# Micromouse_controller_v008.net
KiCad netlist of a schematic drawn in EAGLE
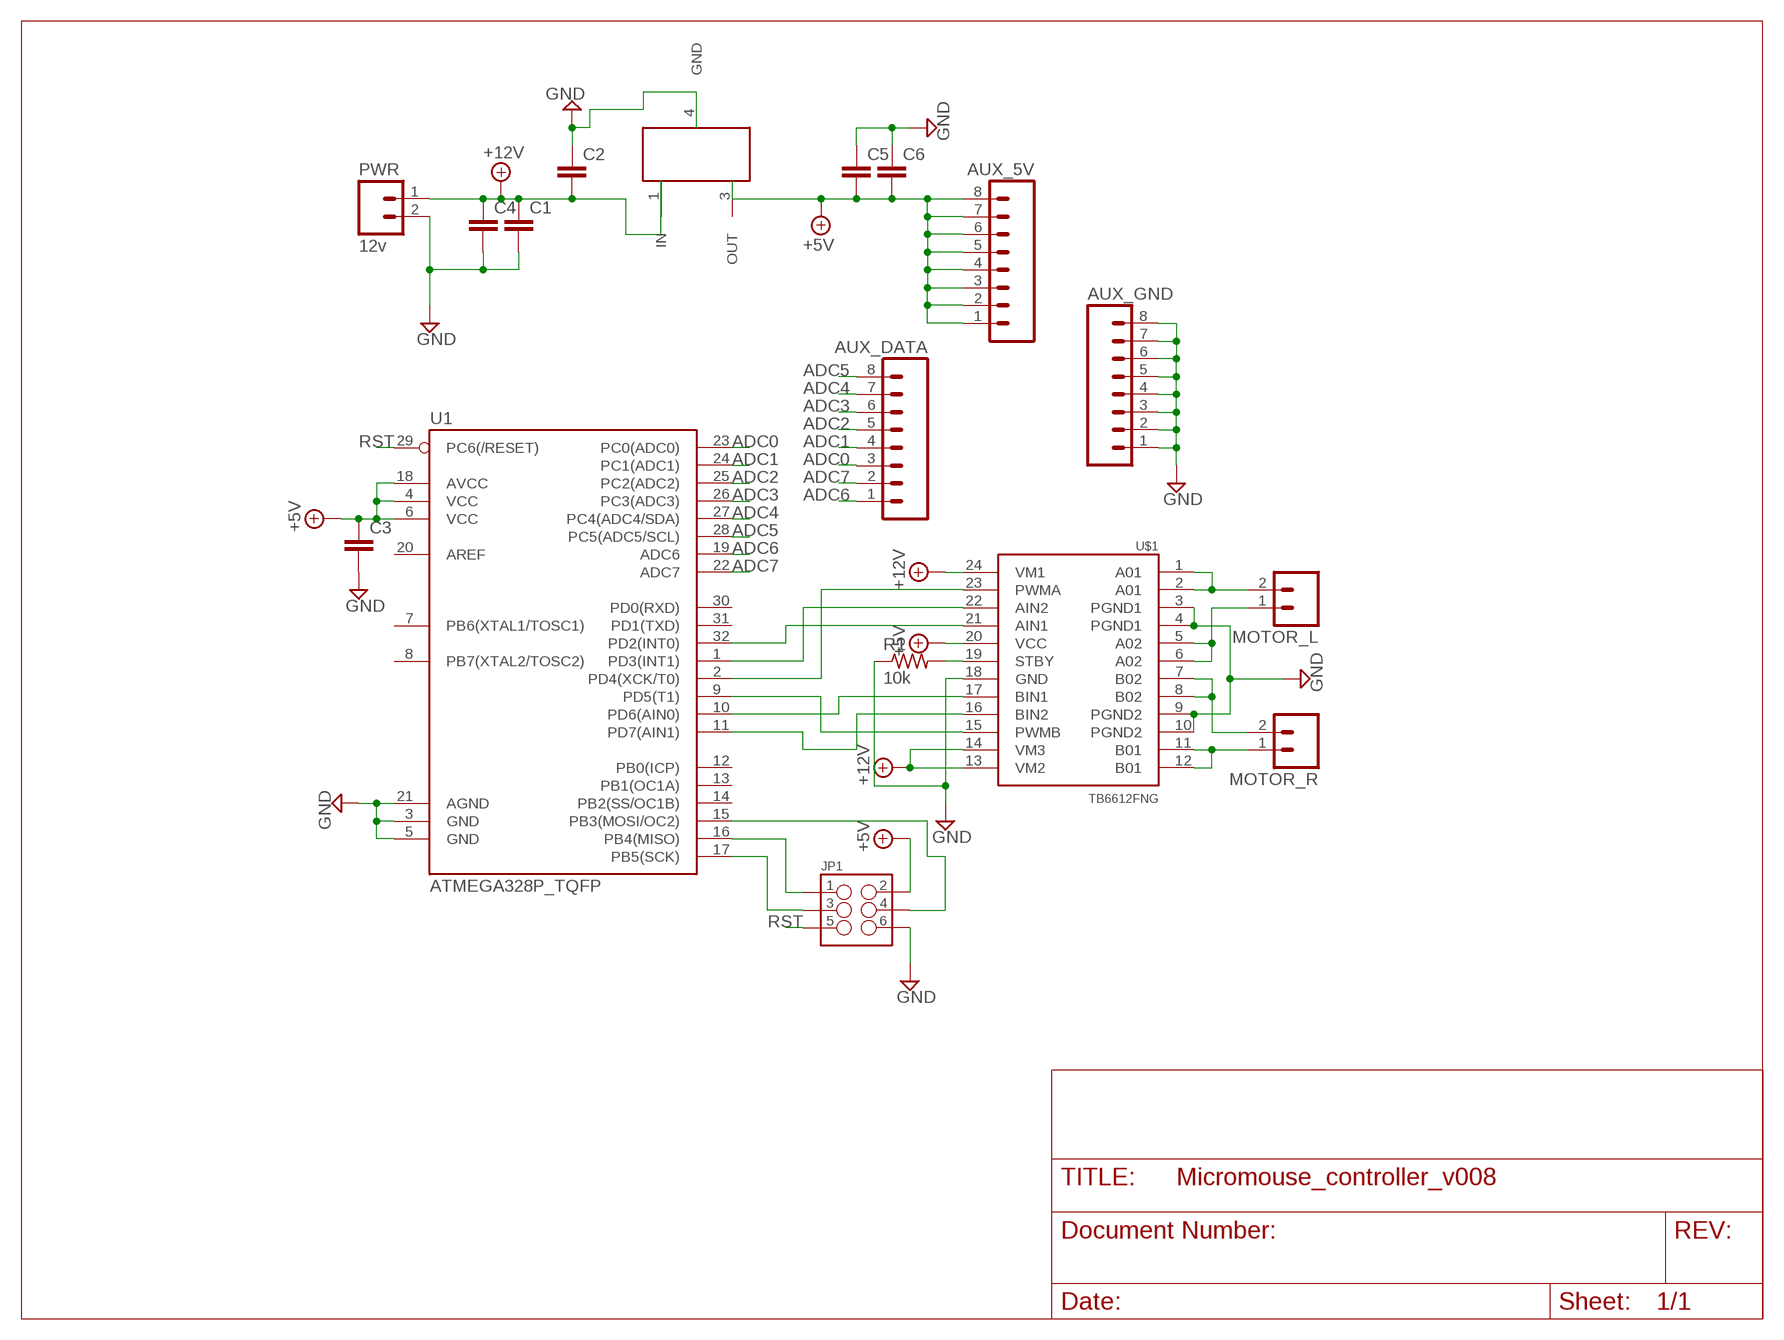
[diagram p0: schematic, sheet 1]

(export (version "E")
  (design (tool "Eeschema 10.0.6"))
  (components
    (comp (ref "AUX_5V")
      (value "M08SMD-STRAIGHT-ALT-FEMALE")
      (footprint "eagle-import:1X08_SMD_ALT")
      (libsource (lib "eagle-import") (part "M08SMD-STRAIGHT-ALT-FEMALE"))
    )
    (comp (ref "AUX_DATA")
      (value "M08SMD-STRAIGHT-ALT-FEMALE")
      (footprint "eagle-import:1X08_SMD_ALT")
      (libsource (lib "eagle-import") (part "M08SMD-STRAIGHT-ALT-FEMALE"))
    )
    (comp (ref "AUX_GND")
      (value "M08SMD-STRAIGHT-ALT-FEMALE")
      (footprint "eagle-import:1X08_SMD_ALT")
      (libsource (lib "eagle-import") (part "M08SMD-STRAIGHT-ALT-FEMALE"))
    )
    (comp (ref "C1")
      (value "CAPSMD")
      (footprint "eagle-import:GRM43D")
      (libsource (lib "eagle-import") (part "CAPSMD"))
    )
    (comp (ref "C2")
      (value "CAPSMD")
      (footprint "eagle-import:GRM43D")
      (libsource (lib "eagle-import") (part "CAPSMD"))
    )
    (comp (ref "C3")
      (value "CAPSMD")
      (footprint "eagle-import:GRM43D")
      (libsource (lib "eagle-import") (part "CAPSMD"))
    )
    (comp (ref "C4")
      (value "CAPSMD")
      (footprint "eagle-import:GRM43D")
      (libsource (lib "eagle-import") (part "CAPSMD"))
    )
    (comp (ref "C5")
      (value "CAPSMD")
      (footprint "eagle-import:GRM43D")
      (libsource (lib "eagle-import") (part "CAPSMD"))
    )
    (comp (ref "C6")
      (value "CAPSMD")
      (footprint "eagle-import:GRM43D")
      (libsource (lib "eagle-import") (part "CAPSMD"))
    )
    (comp (ref "IC2")
      (value "TA4805BF")
      (footprint "eagle-import:DPAK")
      (libsource (lib "eagle-import") (part "TA4805BF"))
    )
    (comp (ref "JP1")
      (value "M03X2FEMALE_SMD")
      (footprint "eagle-import:2X3_SMD")
      (libsource (lib "eagle-import") (part "M03X2FEMALE_SMD"))
    )
    (comp (ref "MOTOR_L")
      (value "M02-JST-2MM-SMT")
      (footprint "eagle-import:JST-2-SMD")
      (libsource (lib "eagle-import") (part "M02-JST-2MM-SMT"))
    )
    (comp (ref "MOTOR_R")
      (value "M02-JST-2MM-SMT")
      (footprint "eagle-import:JST-2-SMD")
      (libsource (lib "eagle-import") (part "M02-JST-2MM-SMT"))
    )
    (comp (ref "PWR")
      (value "12v")
      (footprint "eagle-import:JST-2-SMD")
      (libsource (lib "eagle-import") (part "M02-JST-2MM-SMT"))
    )
    (comp (ref "R1")
      (value "10k")
      (footprint "eagle-import:R0603")
      (libsource (lib "eagle-import") (part "R-US_R0603"))
    )
    (comp (ref "U$1")
      (value "TB6612FNG")
      (footprint "eagle-import:SSOP24")
      (libsource (lib "eagle-import") (part "TB6612FNG"))
    )
    (comp (ref "U1")
      (value "ATMEGA328P_TQFP")
      (footprint "eagle-import:TQFP32-08")
      (libsource (lib "eagle-import") (part "ATMEGA328P_TQFP"))
    )
  )
  (nets
    (net (code "1") (name "+5V") (class "Default")
      (node (ref "AUX_5V") (pin "1") (pinfunction "1_1") (pintype "passive"))
      (node (ref "AUX_5V") (pin "2") (pinfunction "2_2") (pintype "passive"))
      (node (ref "AUX_5V") (pin "3") (pinfunction "3_3") (pintype "passive"))
      (node (ref "AUX_5V") (pin "4") (pinfunction "4_4") (pintype "passive"))
      (node (ref "AUX_5V") (pin "5") (pinfunction "5_5") (pintype "passive"))
      (node (ref "AUX_5V") (pin "6") (pinfunction "6_6") (pintype "passive"))
      (node (ref "AUX_5V") (pin "7") (pinfunction "7_7") (pintype "passive"))
      (node (ref "AUX_5V") (pin "8") (pinfunction "8_8") (pintype "passive"))
      (node (ref "C3") (pin "A") (pinfunction "1_A") (pintype "passive"))
      (node (ref "C5") (pin "C") (pinfunction "2_C") (pintype "passive"))
      (node (ref "C6") (pin "C") (pinfunction "2_C") (pintype "passive"))
      (node (ref "IC2") (pin "3") (pinfunction "OUT_3") (pintype "bidirectional"))
      (node (ref "JP1") (pin "2") (pinfunction "2_2") (pintype "bidirectional"))
      (node (ref "U$1") (pin "20") (pinfunction "VCC_20") (pintype "bidirectional"))
      (node (ref "U1") (pin "18") (pinfunction "AVCC_18") (pintype "bidirectional"))
      (node (ref "U1") (pin "4") (pinfunction "VCC_4") (pintype "bidirectional"))
      (node (ref "U1") (pin "6") (pinfunction "VCC_6") (pintype "bidirectional"))
    )
    (net (code "2") (name "+12V") (class "Default")
      (node (ref "C1") (pin "A") (pinfunction "1_A") (pintype "passive"))
      (node (ref "C2") (pin "C") (pinfunction "2_C") (pintype "passive"))
      (node (ref "C4") (pin "A") (pinfunction "1_A") (pintype "passive"))
      (node (ref "IC2") (pin "1") (pinfunction "IN_1") (pintype "bidirectional"))
      (node (ref "PWR") (pin "1") (pinfunction "2_1") (pintype "passive"))
      (node (ref "U$1") (pin "13") (pinfunction "VM2_13") (pintype "bidirectional"))
      (node (ref "U$1") (pin "14") (pinfunction "VM3_14") (pintype "bidirectional"))
      (node (ref "U$1") (pin "24") (pinfunction "VM1_24") (pintype "bidirectional"))
    )
    (net (code "3") (name "/ADC0") (class "Default")
      (node (ref "AUX_DATA") (pin "3") (pinfunction "3_3") (pintype "passive"))
      (node (ref "U1") (pin "23") (pinfunction "PC0(ADC0)_23") (pintype "bidirectional"))
    )
    (net (code "4") (name "/ADC1") (class "Default")
      (node (ref "AUX_DATA") (pin "4") (pinfunction "4_4") (pintype "passive"))
      (node (ref "U1") (pin "24") (pinfunction "PC1(ADC1)_24") (pintype "bidirectional"))
    )
    (net (code "5") (name "/ADC2") (class "Default")
      (node (ref "AUX_DATA") (pin "5") (pinfunction "5_5") (pintype "passive"))
      (node (ref "U1") (pin "25") (pinfunction "PC2(ADC2)_25") (pintype "bidirectional"))
    )
    (net (code "6") (name "/ADC3") (class "Default")
      (node (ref "AUX_DATA") (pin "6") (pinfunction "6_6") (pintype "passive"))
      (node (ref "U1") (pin "26") (pinfunction "PC3(ADC3)_26") (pintype "bidirectional"))
    )
    (net (code "7") (name "/ADC4") (class "Default")
      (node (ref "AUX_DATA") (pin "7") (pinfunction "7_7") (pintype "passive"))
      (node (ref "U1") (pin "27") (pinfunction "PC4(ADC4/SDA)_27") (pintype "bidirectional"))
    )
    (net (code "8") (name "/ADC5") (class "Default")
      (node (ref "AUX_DATA") (pin "8") (pinfunction "8_8") (pintype "passive"))
      (node (ref "U1") (pin "28") (pinfunction "PC5(ADC5/SCL)_28") (pintype "bidirectional"))
    )
    (net (code "9") (name "/ADC6") (class "Default")
      (node (ref "AUX_DATA") (pin "1") (pinfunction "1_1") (pintype "passive"))
      (node (ref "U1") (pin "19") (pinfunction "ADC6_19") (pintype "bidirectional"))
    )
    (net (code "10") (name "/ADC7") (class "Default")
      (node (ref "AUX_DATA") (pin "2") (pinfunction "2_2") (pintype "passive"))
      (node (ref "U1") (pin "22") (pinfunction "ADC7_22") (pintype "bidirectional"))
    )
    (net (code "11") (name "/RST") (class "Default")
      (node (ref "JP1") (pin "5") (pinfunction "5_5") (pintype "bidirectional"))
      (node (ref "U1") (pin "29") (pinfunction "PC6(/RESET)_29") (pintype "bidirectional"))
    )
    (net (code "12") (name "GND") (class "Default")
      (node (ref "AUX_GND") (pin "1") (pinfunction "1_1") (pintype "passive"))
      (node (ref "AUX_GND") (pin "2") (pinfunction "2_2") (pintype "passive"))
      (node (ref "AUX_GND") (pin "3") (pinfunction "3_3") (pintype "passive"))
      (node (ref "AUX_GND") (pin "4") (pinfunction "4_4") (pintype "passive"))
      (node (ref "AUX_GND") (pin "5") (pinfunction "5_5") (pintype "passive"))
      (node (ref "AUX_GND") (pin "6") (pinfunction "6_6") (pintype "passive"))
      (node (ref "AUX_GND") (pin "7") (pinfunction "7_7") (pintype "passive"))
      (node (ref "AUX_GND") (pin "8") (pinfunction "8_8") (pintype "passive"))
      (node (ref "C1") (pin "C") (pinfunction "2_C") (pintype "passive"))
      (node (ref "C2") (pin "A") (pinfunction "1_A") (pintype "passive"))
      (node (ref "C3") (pin "C") (pinfunction "2_C") (pintype "passive"))
      (node (ref "C4") (pin "C") (pinfunction "2_C") (pintype "passive"))
      (node (ref "C5") (pin "A") (pinfunction "1_A") (pintype "passive"))
      (node (ref "C6") (pin "A") (pinfunction "1_A") (pintype "passive"))
      (node (ref "IC2") (pin "4") (pinfunction "GND_4") (pintype "bidirectional"))
      (node (ref "JP1") (pin "6") (pinfunction "6_6") (pintype "bidirectional"))
      (node (ref "PWR") (pin "2") (pinfunction "1_2") (pintype "passive"))
      (node (ref "R1") (pin "1") (pinfunction "1_1") (pintype "passive"))
      (node (ref "U$1") (pin "10") (pinfunction "PGND2_10") (pintype "bidirectional"))
      (node (ref "U$1") (pin "18") (pinfunction "GND_18") (pintype "bidirectional"))
      (node (ref "U$1") (pin "3") (pinfunction "PGND1_3") (pintype "bidirectional"))
      (node (ref "U$1") (pin "4") (pinfunction "PGND1_4") (pintype "bidirectional"))
      (node (ref "U$1") (pin "9") (pinfunction "PGND2_9") (pintype "bidirectional"))
      (node (ref "U1") (pin "21") (pinfunction "AGND_21") (pintype "bidirectional"))
      (node (ref "U1") (pin "3") (pinfunction "GND_3") (pintype "bidirectional"))
      (node (ref "U1") (pin "5") (pinfunction "GND_5") (pintype "bidirectional"))
    )
    (net (code "13") (name "Net-(MOTOR_L-1)") (class "Default")
      (node (ref "MOTOR_L") (pin "2") (pinfunction "1_2") (pintype "passive"))
      (node (ref "U$1") (pin "1") (pinfunction "A01_1") (pintype "bidirectional"))
      (node (ref "U$1") (pin "2") (pinfunction "A01_2") (pintype "bidirectional"))
    )
    (net (code "14") (name "Net-(MOTOR_L-2)") (class "Default")
      (node (ref "MOTOR_L") (pin "1") (pinfunction "2_1") (pintype "passive"))
      (node (ref "U$1") (pin "5") (pinfunction "A02_5") (pintype "bidirectional"))
      (node (ref "U$1") (pin "6") (pinfunction "A02_6") (pintype "bidirectional"))
    )
    (net (code "15") (name "Net-(MOTOR_R-1)") (class "Default")
      (node (ref "MOTOR_R") (pin "2") (pinfunction "1_2") (pintype "passive"))
      (node (ref "U$1") (pin "7") (pinfunction "B02_7") (pintype "bidirectional"))
      (node (ref "U$1") (pin "8") (pinfunction "B02_8") (pintype "bidirectional"))
    )
    (net (code "16") (name "Net-(MOTOR_R-2)") (class "Default")
      (node (ref "MOTOR_R") (pin "1") (pinfunction "2_1") (pintype "passive"))
      (node (ref "U$1") (pin "11") (pinfunction "B01_11") (pintype "bidirectional"))
      (node (ref "U$1") (pin "12") (pinfunction "B01_12") (pintype "bidirectional"))
    )
    (net (code "17") (name "Net-(U$1-AIN1)") (class "Default")
      (node (ref "U$1") (pin "21") (pinfunction "AIN1_21") (pintype "bidirectional"))
      (node (ref "U1") (pin "32") (pinfunction "PD2(INT0)_32") (pintype "bidirectional"))
    )
    (net (code "18") (name "Net-(U$1-AIN2)") (class "Default")
      (node (ref "U$1") (pin "22") (pinfunction "AIN2_22") (pintype "bidirectional"))
      (node (ref "U1") (pin "1") (pinfunction "PD3(INT1)_1") (pintype "bidirectional"))
    )
    (net (code "19") (name "Net-(U$1-BIN1)") (class "Default")
      (node (ref "U$1") (pin "17") (pinfunction "BIN1_17") (pintype "bidirectional"))
      (node (ref "U1") (pin "10") (pinfunction "PD6(AIN0)_10") (pintype "bidirectional"))
    )
    (net (code "20") (name "Net-(U$1-BIN2)") (class "Default")
      (node (ref "U$1") (pin "16") (pinfunction "BIN2_16") (pintype "bidirectional"))
      (node (ref "U1") (pin "11") (pinfunction "PD7(AIN1)_11") (pintype "bidirectional"))
    )
    (net (code "21") (name "Net-(U$1-PWMA)") (class "Default")
      (node (ref "U$1") (pin "23") (pinfunction "PWMA_23") (pintype "bidirectional"))
      (node (ref "U1") (pin "2") (pinfunction "PD4(XCK/T0)_2") (pintype "bidirectional"))
    )
    (net (code "22") (name "Net-(U$1-PWMB)") (class "Default")
      (node (ref "U$1") (pin "15") (pinfunction "PWMB_15") (pintype "bidirectional"))
      (node (ref "U1") (pin "9") (pinfunction "PD5(T1)_9") (pintype "bidirectional"))
    )
    (net (code "23") (name "Net-(U$1-STBY)") (class "Default")
      (node (ref "R1") (pin "2") (pinfunction "2_2") (pintype "passive"))
      (node (ref "U$1") (pin "19") (pinfunction "STBY_19") (pintype "bidirectional"))
    )
    (net (code "24") (name "Net-(U1-PB3(MOSI{slash}OC2))") (class "Default")
      (node (ref "JP1") (pin "4") (pinfunction "4_4") (pintype "bidirectional"))
      (node (ref "U1") (pin "15") (pinfunction "PB3(MOSI/OC2)_15") (pintype "bidirectional"))
    )
    (net (code "25") (name "Net-(U1-PB4(MISO))") (class "Default")
      (node (ref "JP1") (pin "1") (pinfunction "1_1") (pintype "bidirectional"))
      (node (ref "U1") (pin "16") (pinfunction "PB4(MISO)_16") (pintype "bidirectional"))
    )
    (net (code "26") (name "Net-(U1-PB5(SCK))") (class "Default")
      (node (ref "JP1") (pin "3") (pinfunction "3_3") (pintype "bidirectional"))
      (node (ref "U1") (pin "17") (pinfunction "PB5(SCK)_17") (pintype "bidirectional"))
    )
    (net (code "27") (name "unconnected-(U1-AREF-Pad20)") (class "Default")
      (node (ref "U1") (pin "20") (pinfunction "AREF_20") (pintype "bidirectional"))
    )
    (net (code "28") (name "unconnected-(U1-PB0(ICP)-Pad12)") (class "Default")
      (node (ref "U1") (pin "12") (pinfunction "PB0(ICP)_12") (pintype "bidirectional"))
    )
    (net (code "29") (name "unconnected-(U1-PB1(OC1A)-Pad13)") (class "Default")
      (node (ref "U1") (pin "13") (pinfunction "PB1(OC1A)_13") (pintype "bidirectional"))
    )
    (net (code "30") (name "unconnected-(U1-PB2(SS{slash}OC1B)-Pad14)") (class "Default")
      (node (ref "U1") (pin "14") (pinfunction "PB2(SS/OC1B)_14") (pintype "bidirectional"))
    )
    (net (code "31") (name "unconnected-(U1-PB6(XTAL1{slash}TOSC1)-Pad7)") (class "Default")
      (node (ref "U1") (pin "7") (pinfunction "PB6(XTAL1/TOSC1)_7") (pintype "bidirectional"))
    )
    (net (code "32") (name "unconnected-(U1-PB7(XTAL2{slash}TOSC2)-Pad8)") (class "Default")
      (node (ref "U1") (pin "8") (pinfunction "PB7(XTAL2/TOSC2)_8") (pintype "bidirectional"))
    )
    (net (code "33") (name "unconnected-(U1-PD0(RXD)-Pad30)") (class "Default")
      (node (ref "U1") (pin "30") (pinfunction "PD0(RXD)_30") (pintype "bidirectional"))
    )
    (net (code "34") (name "unconnected-(U1-PD1(TXD)-Pad31)") (class "Default")
      (node (ref "U1") (pin "31") (pinfunction "PD1(TXD)_31") (pintype "bidirectional"))
    )
  )
)
